# 12_B_TO_B.net
KiCad netlist of a schematic drawn in Altium Designer
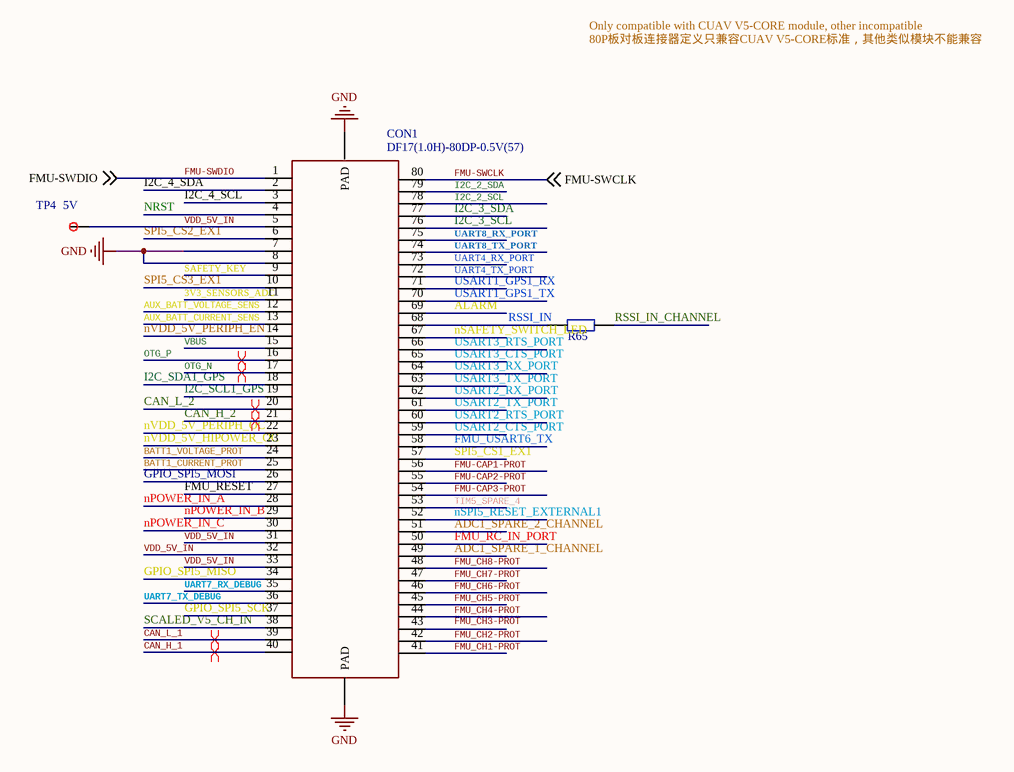
[diagram p0: 12_B_TO_B.SchDoc]

(export (version "E")
  (design (tool "Eeschema 10.0.6"))
  (components
    (comp (ref "CON1")
      (value "DF17(1.0H)-80DP-0.5V(57)")
      (footprint "DF17(1.0H)-80DP-0.5V(57)")
      (libsource (lib "CUAV") (part "DF17(1.0H)-80DP-0.5V(57)"))
    )
    (comp (ref "R65")
      (value "0402R100R")
      (footprint "0402R")
      (description "0402R100R 1%")
      (libsource (lib "CUAV") (part "0402R100R"))
    )
    (comp (ref "TP4")
      (value "5V")
      (footprint "TP0.75")
      (description "TP_0.75MM")
      (libsource (lib "CUAV") (part "TP_0.75"))
    )
  )
  (nets
    (net (code "1") (name "/3V3_SENSORS_ADC") (class "Default")
      (node (ref "CON1") (pin "11") (pintype "passive"))
    )
    (net (code "3") (name "/ADC1_SPARE_1_CHANNEL") (class "Default")
      (node (ref "CON1") (pin "49") (pintype "passive"))
    )
    (net (code "4") (name "/ADC1_SPARE_2_CHANNEL") (class "Default")
      (node (ref "CON1") (pin "51") (pintype "passive"))
    )
    (net (code "5") (name "/ALARM") (class "Default") (node (ref "CON1") (pin "69") (pintype "passive")))
    (net (code "6") (name "/AUX_BATT_CURRENT_SENS") (class "Default")
      (node (ref "CON1") (pin "13") (pintype "passive"))
    )
    (net (code "7") (name "/AUX_BATT_VOLTAGE_SENS") (class "Default")
      (node (ref "CON1") (pin "12") (pintype "passive"))
    )
    (net (code "8") (name "/BATT1_CURRENT_PROT") (class "Default")
      (node (ref "CON1") (pin "25") (pintype "passive"))
    )
    (net (code "9") (name "/BATT1_VOLTAGE_PROT") (class "Default")
      (node (ref "CON1") (pin "24") (pintype "passive"))
    )
    (net (code "10") (name "/CAN_H_1") (class "Default") (node (ref "CON1") (pin "40") (pintype "passive")))
    (net (code "11") (name "/CAN_H_2") (class "Default") (node (ref "CON1") (pin "21") (pintype "passive")))
    (net (code "12") (name "/CAN_L_1") (class "Default") (node (ref "CON1") (pin "39") (pintype "passive")))
    (net (code "13") (name "/CAN_L_2") (class "Default") (node (ref "CON1") (pin "20") (pintype "passive")))
    (net (code "14") (name "/FMU-CAP1-PROT") (class "Default")
      (node (ref "CON1") (pin "56") (pintype "passive"))
    )
    (net (code "15") (name "/FMU-CAP2-PROT") (class "Default")
      (node (ref "CON1") (pin "55") (pintype "passive"))
    )
    (net (code "16") (name "/FMU-CAP3-PROT") (class "Default")
      (node (ref "CON1") (pin "54") (pintype "passive"))
    )
    (net (code "17") (name "/FMU_CH1-PROT") (class "Default")
      (node (ref "CON1") (pin "41") (pintype "passive"))
    )
    (net (code "18") (name "/FMU_CH2-PROT") (class "Default")
      (node (ref "CON1") (pin "42") (pintype "passive"))
    )
    (net (code "20") (name "/FMU_CH4-PROT") (class "Default")
      (node (ref "CON1") (pin "44") (pintype "passive"))
    )
    (net (code "21") (name "/FMU_CH5-PROT") (class "Default")
      (node (ref "CON1") (pin "45") (pintype "passive"))
    )
    (net (code "22") (name "/FMU_CH6-PROT") (class "Default")
      (node (ref "CON1") (pin "46") (pintype "passive"))
    )
    (net (code "23") (name "/FMU_CH7-PROT") (class "Default")
      (node (ref "CON1") (pin "47") (pintype "passive"))
    )
    (net (code "24") (name "/FMU_CH8-PROT") (class "Default")
      (node (ref "CON1") (pin "48") (pintype "passive"))
    )
    (net (code "25") (name "/FMU_RC_IN_PORT") (class "Default")
      (node (ref "CON1") (pin "50") (pintype "passive"))
    )
    (net (code "26") (name "/FMU_RESET") (class "Default") (node (ref "CON1") (pin "27") (pintype "passive")))
    (net (code "27") (name "/FMU_USART6_TX") (class "Default")
      (node (ref "CON1") (pin "58") (pintype "passive"))
    )
    (net (code "28") (name "/GPIO_SPI5_MISO") (class "Default")
      (node (ref "CON1") (pin "34") (pintype "passive"))
    )
    (net (code "29") (name "/GPIO_SPI5_MOSI") (class "Default")
      (node (ref "CON1") (pin "26") (pintype "passive"))
    )
    (net (code "30") (name "/GPIO_SPI5_SCK") (class "Default")
      (node (ref "CON1") (pin "37") (pintype "passive"))
    )
    (net (code "31") (name "/I2C_2_SCL") (class "Default") (node (ref "CON1") (pin "78") (pintype "passive")))
    (net (code "32") (name "/I2C_2_SDA") (class "Default") (node (ref "CON1") (pin "79") (pintype "passive")))
    (net (code "33") (name "/I2C_3_SCL") (class "Default") (node (ref "CON1") (pin "76") (pintype "passive")))
    (net (code "34") (name "/I2C_3_SDA") (class "Default") (node (ref "CON1") (pin "77") (pintype "passive")))
    (net (code "35") (name "/I2C_4_SCL") (class "Default") (node (ref "CON1") (pin "3") (pintype "passive")))
    (net (code "36") (name "/I2C_4_SDA") (class "Default") (node (ref "CON1") (pin "2") (pintype "passive")))
    (net (code "37") (name "/I2C_SCL1_GPS") (class "Default")
      (node (ref "CON1") (pin "19") (pintype "passive"))
    )
    (net (code "38") (name "/I2C_SDA1_GPS") (class "Default")
      (node (ref "CON1") (pin "18") (pintype "passive"))
    )
    (net (code "39") (name "/NRST") (class "Default") (node (ref "CON1") (pin "4") (pintype "passive")))
    (net (code "40") (name "/OTG_N") (class "Default") (node (ref "CON1") (pin "17") (pintype "passive")))
    (net (code "41") (name "/OTG_P") (class "Default") (node (ref "CON1") (pin "16") (pintype "passive")))
    (net (code "43") (name "/RSSI_IN") (class "Default")
      (node (ref "CON1") (pin "68") (pintype "passive"))
      (node (ref "R65") (pin "2") (pintype "passive"))
    )
    (net (code "44") (name "/RSSI_IN_CHANNEL") (class "Default")
      (node (ref "R65") (pin "1") (pintype "passive"))
    )
    (net (code "45") (name "/SAFETY_KEY") (class "Default") (node (ref "CON1") (pin "9") (pintype "passive")))
    (net (code "46") (name "/SCALED_V5_CH_IN") (class "Default")
      (node (ref "CON1") (pin "38") (pintype "passive"))
    )
    (net (code "47") (name "/SPI5_CS1_EX1") (class "Default")
      (node (ref "CON1") (pin "57") (pintype "passive"))
    )
    (net (code "48") (name "/SPI5_CS2_EX1") (class "Default")
      (node (ref "CON1") (pin "6") (pintype "passive"))
    )
    (net (code "49") (name "/SPI5_CS3_EX1") (class "Default")
      (node (ref "CON1") (pin "10") (pintype "passive"))
    )
    (net (code "50") (name "/TIM5_SPARE_4") (class "Default")
      (node (ref "CON1") (pin "53") (pintype "passive"))
    )
    (net (code "51") (name "/UART4_RX_PORT") (class "Default")
      (node (ref "CON1") (pin "73") (pintype "passive"))
    )
    (net (code "52") (name "/UART4_TX_PORT") (class "Default")
      (node (ref "CON1") (pin "72") (pintype "passive"))
    )
    (net (code "53") (name "/UART7_RX_DEBUG") (class "Default")
      (node (ref "CON1") (pin "35") (pintype "passive"))
    )
    (net (code "54") (name "/UART7_TX_DEBUG") (class "Default")
      (node (ref "CON1") (pin "36") (pintype "passive"))
    )
    (net (code "55") (name "/UART8_RX_PORT") (class "Default")
      (node (ref "CON1") (pin "75") (pintype "passive"))
    )
    (net (code "56") (name "/UART8_TX_PORT") (class "Default")
      (node (ref "CON1") (pin "74") (pintype "passive"))
    )
    (net (code "57") (name "/USART1_GPS1_RX") (class "Default")
      (node (ref "CON1") (pin "71") (pintype "passive"))
    )
    (net (code "58") (name "/USART1_GPS1_TX") (class "Default")
      (node (ref "CON1") (pin "70") (pintype "passive"))
    )
    (net (code "59") (name "/USART2_CTS_PORT") (class "Default")
      (node (ref "CON1") (pin "59") (pintype "passive"))
    )
    (net (code "60") (name "/USART2_RTS_PORT") (class "Default")
      (node (ref "CON1") (pin "60") (pintype "passive"))
    )
    (net (code "61") (name "/USART2_RX_PORT") (class "Default")
      (node (ref "CON1") (pin "62") (pintype "passive"))
    )
    (net (code "62") (name "/USART2_TX_PORT") (class "Default")
      (node (ref "CON1") (pin "61") (pintype "passive"))
    )
    (net (code "63") (name "/USART3_CTS_PORT") (class "Default")
      (node (ref "CON1") (pin "65") (pintype "passive"))
    )
    (net (code "64") (name "/USART3_RTS_PORT") (class "Default")
      (node (ref "CON1") (pin "66") (pintype "passive"))
    )
    (net (code "65") (name "/USART3_RX_PORT") (class "Default")
      (node (ref "CON1") (pin "64") (pintype "passive"))
    )
    (net (code "66") (name "/USART3_TX_PORT") (class "Default")
      (node (ref "CON1") (pin "63") (pintype "passive"))
    )
    (net (code "67") (name "/VBUS") (class "Default") (node (ref "CON1") (pin "15") (pintype "passive")))
    (net (code "68") (name "/VDD_5V_IN") (class "Default")
      (node (ref "CON1") (pin "31") (pintype "passive"))
      (node (ref "CON1") (pin "32") (pintype "passive"))
      (node (ref "CON1") (pin "33") (pintype "passive"))
      (node (ref "CON1") (pin "5") (pintype "passive"))
      (node (ref "TP4") (pin "0") (pintype "passive"))
    )
    (net (code "69") (name "/nPOWER_IN_A") (class "Default")
      (node (ref "CON1") (pin "28") (pintype "passive"))
    )
    (net (code "70") (name "/nPOWER_IN_B") (class "Default")
      (node (ref "CON1") (pin "29") (pintype "passive"))
    )
    (net (code "71") (name "/nPOWER_IN_C") (class "Default")
      (node (ref "CON1") (pin "30") (pintype "passive"))
    )
    (net (code "72") (name "/nSAFETY_SWITCH_LED") (class "Default")
      (node (ref "CON1") (pin "67") (pintype "passive"))
    )
    (net (code "73") (name "/nSPI5_RESET_EXTERNAL1") (class "Default")
      (node (ref "CON1") (pin "52") (pintype "passive"))
    )
    (net (code "74") (name "/nVDD_5V_HIPOWER_OC") (class "Default")
      (node (ref "CON1") (pin "23") (pintype "passive"))
    )
    (net (code "75") (name "/nVDD_5V_PERIPH_EN") (class "Default")
      (node (ref "CON1") (pin "14") (pintype "passive"))
    )
    (net (code "76") (name "/nVDD_5V_PERIPH_OC") (class "Default")
      (node (ref "CON1") (pin "22") (pintype "passive"))
    )
    (net (code "77") (name "FMU-SWCLK") (class "Default") (node (ref "CON1") (pin "80") (pintype "passive")))
    (net (code "78") (name "FMU-SWDIO") (class "Default") (node (ref "CON1") (pin "1") (pintype "passive")))
    (net (code "79") (name "GND") (class "Default")
      (node (ref "CON1") (pin "7") (pintype "passive"))
      (node (ref "CON1") (pin "8") (pintype "passive"))
      (node (ref "CON1") (pin "PAD") (pinfunction "PAD_PAD") (pintype "passive"))
    )
    (net (code "80") (name "unconnected-(CON1-Pad43)") (class "Default")
      (node (ref "CON1") (pin "43") (pintype "passive"))
    )
  )
)
